# LAUNCHXL-F28377S_3.net
KiCad netlist of a schematic drawn in Altium Designer
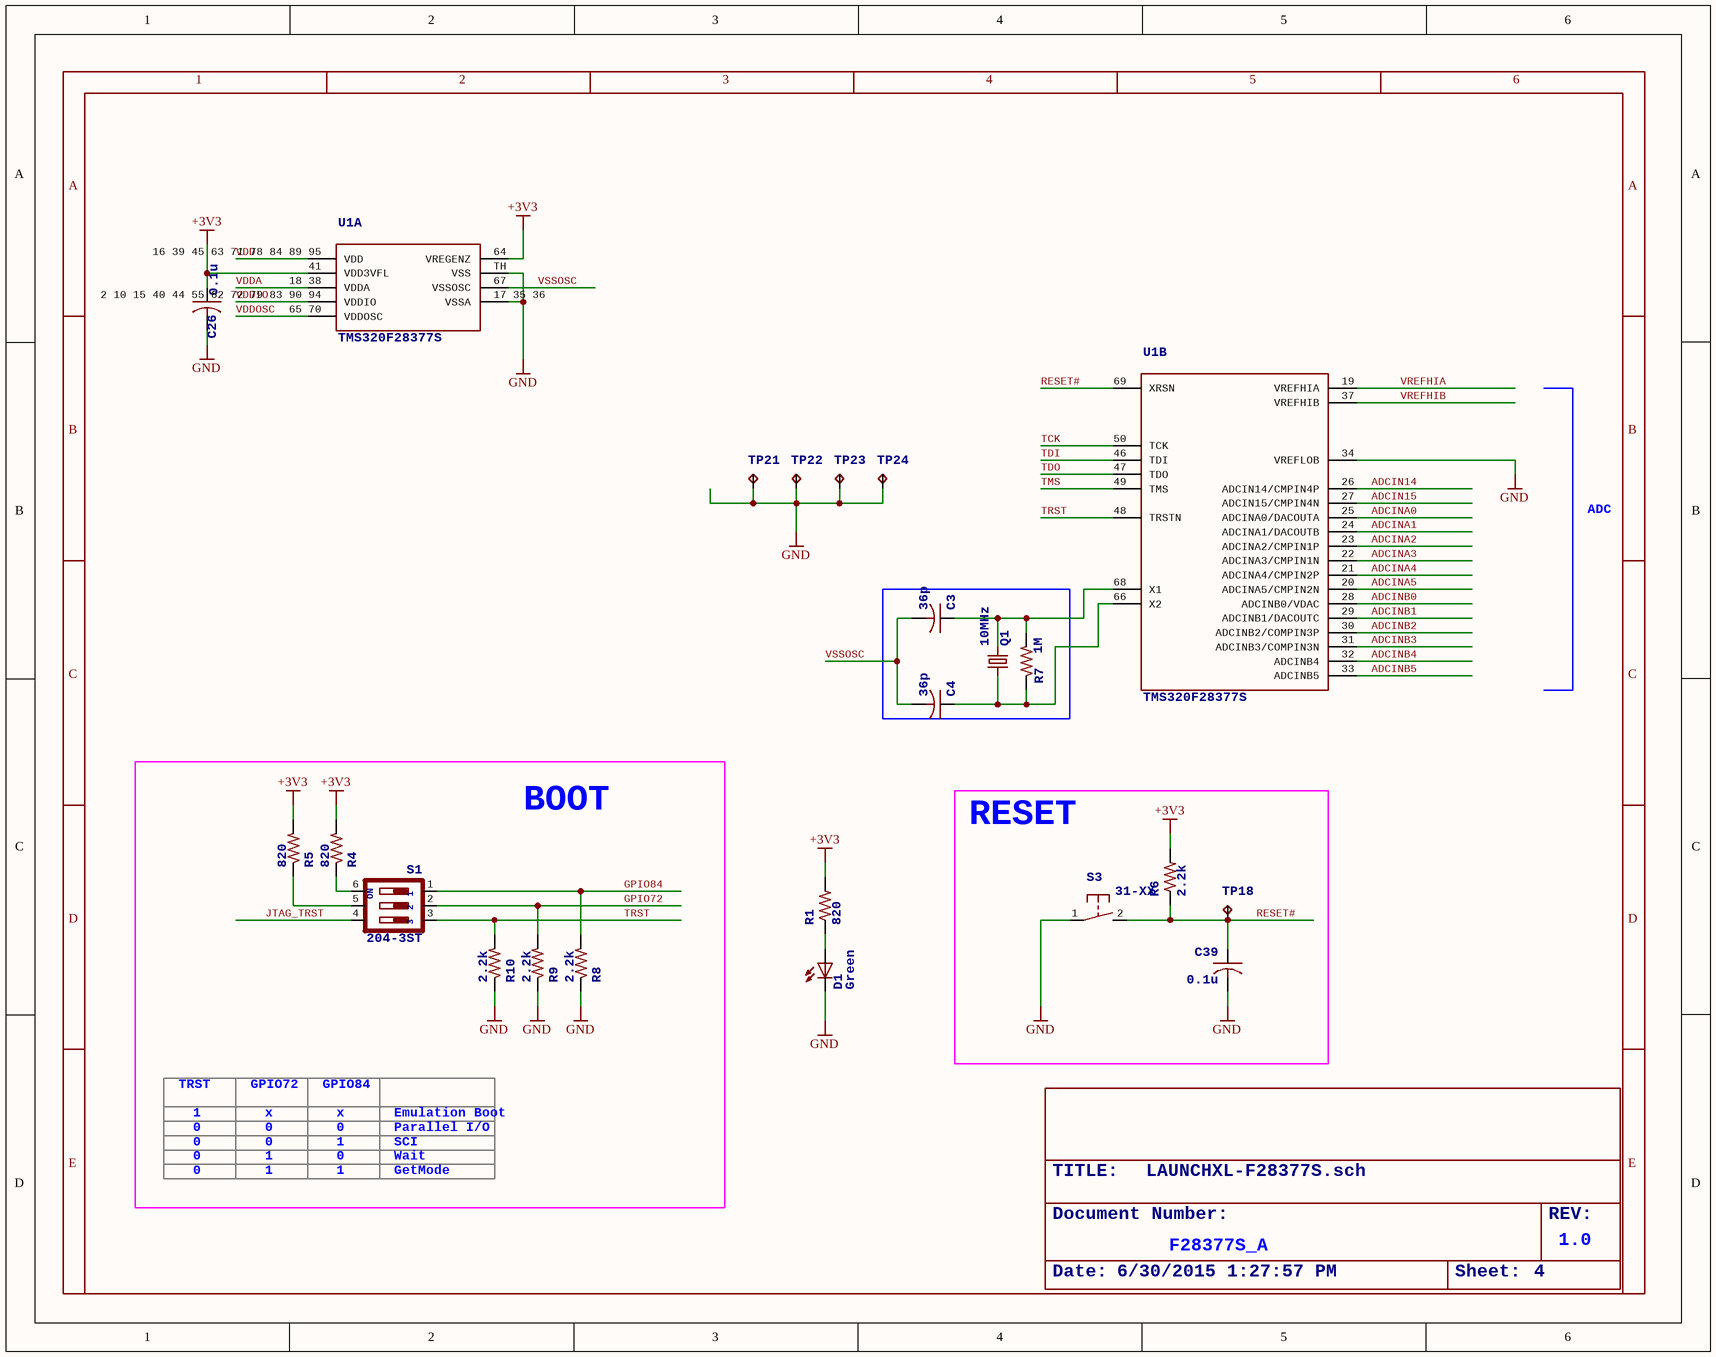
[diagram p0: LAUNCHXL-F28377S_3.SchDoc]

(export (version "E")
  (design (tool "Eeschema 10.0.6"))
  (components
    (comp (ref "C3")
      (value "36p")
      (footprint "C0402")
      (description "<B>CAPACITOR</B>, American symbol")
      (libsource (lib "rcl") (part "C-USC0402"))
    )
    (comp (ref "C4")
      (value "36p")
      (footprint "C0402")
      (description "<B>CAPACITOR</B>, American symbol")
      (libsource (lib "rcl") (part "C-USC0402"))
    )
    (comp (ref "C26")
      (value "0.1u")
      (footprint "C0402")
      (description "<B>CAPACITOR</B>, American symbol")
      (libsource (lib "rcl") (part "C-USC0402"))
    )
    (comp (ref "C39")
      (value "0.1u")
      (footprint "C0402")
      (description "<B>CAPACITOR</B>, American symbol")
      (libsource (lib "rcl") (part "C-USC0402"))
    )
    (comp (ref "D1")
      (value "Green")
      (footprint "CHIP-LED0603")
      (libsource (lib "led") (part "LEDCHIP-LED0603"))
    )
    (comp (ref "Q1")
      (value "10MHz")
      (footprint "HC49/S")
      (description "<b>CRYSTAL</b>")
      (libsource (lib "crystal") (part "CRYSTALHC49S"))
    )
    (comp (ref "R1")
      (value "820")
      (footprint "R0402")
      (description "<B>RESISTOR</B>, American symbol")
      (libsource (lib "rcl") (part "R-US_R0402"))
    )
    (comp (ref "R4")
      (value "820")
      (footprint "R0402")
      (description "<B>RESISTOR</B>, American symbol")
      (libsource (lib "rcl") (part "R-US_R0402"))
    )
    (comp (ref "R5")
      (value "820")
      (footprint "R0402")
      (description "<B>RESISTOR</B>, American symbol")
      (libsource (lib "rcl") (part "R-US_R0402"))
    )
    (comp (ref "R6")
      (value "2.2k")
      (footprint "R0402")
      (description "<B>RESISTOR</B>, American symbol")
      (libsource (lib "rcl") (part "R-US_R0402"))
    )
    (comp (ref "R7")
      (value "1M")
      (footprint "R0402")
      (description "<B>RESISTOR</B>, American symbol")
      (libsource (lib "rcl") (part "R-US_R0402"))
    )
    (comp (ref "R8")
      (value "2.2k")
      (footprint "R0402")
      (description "<B>RESISTOR</B>, American symbol")
      (libsource (lib "rcl") (part "R-US_R0402"))
    )
    (comp (ref "R9")
      (value "2.2k")
      (footprint "R0402")
      (description "<B>RESISTOR</B>, American symbol")
      (libsource (lib "rcl") (part "R-US_R0402"))
    )
    (comp (ref "R10")
      (value "2.2k")
      (footprint "R0402")
      (description "<B>RESISTOR</B>, American symbol")
      (libsource (lib "rcl") (part "R-US_R0402"))
    )
    (comp (ref "S1")
      (value "204-3ST")
      (footprint "CTS-219-03")
      (fields (field (name "1") "1") (field (name "2") "2") (field (name "3") "3") (field (name "ON") "ON"))
      (libsource (lib "switch-dil") (part "219-03*"))
    )
    (comp (ref "S3")
      (value "31-XX")
      (footprint "B3F-31XX")
      (description "<b>OMRON SWITCH</b>")
      (fields (field (name "MPN") "B3F-3100"))
      (libsource (lib "switch-omron") (part "31-XX"))
    )
    (comp (ref "TP18")
      (value "TESTPAD_TPB1,27")
      (footprint "TESTPAD_B1,27")
      (description "<b>Test pad</b>")
      (libsource (lib "RF430FRL152H_EVM_a") (part "TESTPAD_TPB1,27"))
    )
    (comp (ref "TP21")
      (value "TESTPAD_TPB1,27")
      (footprint "TESTPAD_B1,27")
      (description "<b>Test pad</b>")
      (libsource (lib "RF430FRL152H_EVM_a") (part "TESTPAD_TPB1,27"))
    )
    (comp (ref "TP22")
      (value "TESTPAD_TPB1,27")
      (footprint "TESTPAD_B1,27")
      (description "<b>Test pad</b>")
      (libsource (lib "RF430FRL152H_EVM_a") (part "TESTPAD_TPB1,27"))
    )
    (comp (ref "TP23")
      (value "TESTPAD_TPB1,27")
      (footprint "TESTPAD_B1,27")
      (description "<b>Test pad</b>")
      (libsource (lib "RF430FRL152H_EVM_a") (part "TESTPAD_TPB1,27"))
    )
    (comp (ref "TP24")
      (value "TESTPAD_TPB1,27")
      (footprint "TESTPAD_B1,27")
      (description "<b>Test pad</b>")
      (libsource (lib "RF430FRL152H_EVM_a") (part "TESTPAD_TPB1,27"))
    )
    (comp (ref "U1")
      (value "TMS320F28377S")
      (footprint "PQFP100_THERMAL")
      (libsource (lib "LAUNCHXL-F28377S") (part "TMS320F28377S"))
    )
  )
  (nets
    (net (code "1") (name "+3V3") (class "Default")
      (node (ref "C26") (pin "1") (pinfunction "1_1") (pintype "passive"))
      (node (ref "R1") (pin "2") (pinfunction "2_2") (pintype "passive"))
      (node (ref "R4") (pin "2") (pinfunction "2_2") (pintype "passive"))
      (node (ref "R5") (pin "2") (pinfunction "2_2") (pintype "passive"))
      (node (ref "R6") (pin "2") (pinfunction "2_2") (pintype "passive"))
      (node (ref "U1") (pin "41") (pinfunction "VDD3VFL_41") (pintype "passive"))
      (node (ref "U1") (pin "64") (pinfunction "VREGENZ_64") (pintype "passive"))
    )
    (net (code "2") (name "/ADCIN14") (class "Default")
      (node (ref "U1") (pin "26") (pinfunction "ADCIN14/CMPIN4P_26") (pintype "passive"))
    )
    (net (code "3") (name "/ADCIN15") (class "Default")
      (node (ref "U1") (pin "27") (pinfunction "ADCIN15/CMPIN4N_27") (pintype "passive"))
    )
    (net (code "4") (name "/ADCINA0") (class "Default")
      (node (ref "U1") (pin "25") (pinfunction "ADCINA0/DACOUTA_25") (pintype "passive"))
    )
    (net (code "5") (name "/ADCINA1") (class "Default")
      (node (ref "U1") (pin "24") (pinfunction "ADCINA1/DACOUTB_24") (pintype "passive"))
    )
    (net (code "6") (name "/ADCINA2") (class "Default")
      (node (ref "U1") (pin "23") (pinfunction "ADCINA2/CMPIN1P_23") (pintype "passive"))
    )
    (net (code "7") (name "/ADCINA3") (class "Default")
      (node (ref "U1") (pin "22") (pinfunction "ADCINA3/CMPIN1N_22") (pintype "passive"))
    )
    (net (code "8") (name "/ADCINA4") (class "Default")
      (node (ref "U1") (pin "21") (pinfunction "ADCINA4/CMPIN2P_21") (pintype "passive"))
    )
    (net (code "9") (name "/ADCINA5") (class "Default")
      (node (ref "U1") (pin "20") (pinfunction "ADCINA5/CMPIN2N_20") (pintype "passive"))
    )
    (net (code "10") (name "/ADCINB0") (class "Default")
      (node (ref "U1") (pin "28") (pinfunction "ADCINB0/VDAC_28") (pintype "passive"))
    )
    (net (code "11") (name "/ADCINB1") (class "Default")
      (node (ref "U1") (pin "29") (pinfunction "ADCINB1/DACOUTC_29") (pintype "passive"))
    )
    (net (code "12") (name "/ADCINB2") (class "Default")
      (node (ref "U1") (pin "30") (pinfunction "ADCINB2/COMPIN3P_30") (pintype "passive"))
    )
    (net (code "13") (name "/ADCINB3") (class "Default")
      (node (ref "U1") (pin "31") (pinfunction "ADCINB3/COMPIN3N_31") (pintype "passive"))
    )
    (net (code "14") (name "/ADCINB4") (class "Default")
      (node (ref "U1") (pin "32") (pinfunction "ADCINB4_32") (pintype "passive"))
    )
    (net (code "15") (name "/ADCINB5") (class "Default")
      (node (ref "U1") (pin "33") (pinfunction "ADCINB5_33") (pintype "passive"))
    )
    (net (code "16") (name "/GPIO72") (class "Default")
      (node (ref "R9") (pin "2") (pinfunction "2_2") (pintype "passive"))
      (node (ref "S1") (pin "2") (pinfunction "2_2") (pintype "passive"))
    )
    (net (code "17") (name "/GPIO84") (class "Default")
      (node (ref "R8") (pin "2") (pinfunction "2_2") (pintype "passive"))
      (node (ref "S1") (pin "1") (pinfunction "1_1") (pintype "passive"))
    )
    (net (code "18") (name "/JTAG_TRST") (class "Default")
      (node (ref "S1") (pin "4") (pinfunction "4_4") (pintype "passive"))
    )
    (net (code "19") (name "/RESET#") (class "Default")
      (node (ref "C39") (pin "1") (pinfunction "1_1") (pintype "passive"))
      (node (ref "R6") (pin "1") (pinfunction "1_1") (pintype "passive"))
      (node (ref "S3") (pin "2") (pinfunction "S_2") (pintype "passive"))
      (node (ref "TP18") (pin "TP") (pinfunction "TP_TP") (pintype "passive"))
      (node (ref "U1") (pin "69") (pinfunction "XRSN_69") (pintype "passive"))
    )
    (net (code "20") (name "/TCK") (class "Default")
      (node (ref "U1") (pin "50") (pinfunction "TCK_50") (pintype "passive"))
    )
    (net (code "21") (name "/TDI") (class "Default")
      (node (ref "U1") (pin "46") (pinfunction "TDI_46") (pintype "passive"))
    )
    (net (code "22") (name "/TDO") (class "Default")
      (node (ref "U1") (pin "47") (pinfunction "TDO_47") (pintype "passive"))
    )
    (net (code "23") (name "/TMS") (class "Default")
      (node (ref "U1") (pin "49") (pinfunction "TMS_49") (pintype "passive"))
    )
    (net (code "24") (name "/TRST") (class "Default")
      (node (ref "R10") (pin "2") (pinfunction "2_2") (pintype "passive"))
      (node (ref "S1") (pin "3") (pinfunction "3_3") (pintype "passive"))
      (node (ref "U1") (pin "48") (pinfunction "TRSTN_48") (pintype "passive"))
    )
    (net (code "25") (name "/VDD") (class "Default")
      (node (ref "U1") (pin "16_39_45_63_71_78_84_89_95") (pinfunction "VDD_16_39_45_63_71_78_84_89_95") (pintype "passive"))
    )
    (net (code "26") (name "/VDDA") (class "Default")
      (node (ref "U1") (pin "18_38") (pinfunction "VDDA_18_38") (pintype "passive"))
    )
    (net (code "27") (name "/VDDIO") (class "Default")
      (node (ref "U1") (pin "2_10_15_40_44_55_62_72_79_83_90_94") (pinfunction "VDDIO_2_10_15_40_44_55_62_72_79_83_90_94") (pintype "passive"))
    )
    (net (code "28") (name "/VDDOSC") (class "Default")
      (node (ref "U1") (pin "65_70") (pinfunction "VDDOSC_65_70") (pintype "passive"))
    )
    (net (code "29") (name "/VREFHIA") (class "Default")
      (node (ref "U1") (pin "19") (pinfunction "VREFHIA_19") (pintype "passive"))
    )
    (net (code "30") (name "/VREFHIB") (class "Default")
      (node (ref "U1") (pin "37") (pinfunction "VREFHIB_37") (pintype "passive"))
    )
    (net (code "31") (name "/VSSOSC") (class "Default")
      (node (ref "C3") (pin "2") (pinfunction "2_2") (pintype "passive"))
      (node (ref "C4") (pin "2") (pinfunction "2_2") (pintype "passive"))
      (node (ref "U1") (pin "67") (pinfunction "VSSOSC_67") (pintype "passive"))
    )
    (net (code "32") (name "GND") (class "Default")
      (node (ref "C26") (pin "2") (pinfunction "2_2") (pintype "passive"))
      (node (ref "C39") (pin "2") (pinfunction "2_2") (pintype "passive"))
      (node (ref "D1") (pin "C") (pinfunction "C_C") (pintype "passive"))
      (node (ref "R10") (pin "1") (pinfunction "1_1") (pintype "passive"))
      (node (ref "R8") (pin "1") (pinfunction "1_1") (pintype "passive"))
      (node (ref "R9") (pin "1") (pinfunction "1_1") (pintype "passive"))
      (node (ref "S3") (pin "1") (pinfunction "P_1") (pintype "passive"))
      (node (ref "TP21") (pin "TP") (pinfunction "TP_TP") (pintype "passive"))
      (node (ref "TP22") (pin "TP") (pinfunction "TP_TP") (pintype "passive"))
      (node (ref "TP23") (pin "TP") (pinfunction "TP_TP") (pintype "passive"))
      (node (ref "TP24") (pin "TP") (pinfunction "TP_TP") (pintype "passive"))
      (node (ref "U1") (pin "17_35_36") (pinfunction "VSSA_17_35_36") (pintype "passive"))
      (node (ref "U1") (pin "34") (pinfunction "VREFLOB_34") (pintype "passive"))
      (node (ref "U1") (pin "TH") (pinfunction "VSS_TH") (pintype "passive"))
    )
    (net (code "33") (name "Net-(D1-PadA)") (class "Default")
      (node (ref "D1") (pin "A") (pinfunction "A_A") (pintype "passive"))
      (node (ref "R1") (pin "1") (pinfunction "1_1") (pintype "passive"))
    )
    (net (code "34") (name "Net-(R4-Pad1)") (class "Default")
      (node (ref "R4") (pin "1") (pinfunction "1_1") (pintype "passive"))
      (node (ref "S1") (pin "6") (pinfunction "6_6") (pintype "passive"))
    )
    (net (code "35") (name "Net-(R5-Pad1)") (class "Default")
      (node (ref "R5") (pin "1") (pinfunction "1_1") (pintype "passive"))
      (node (ref "S1") (pin "5") (pinfunction "5_5") (pintype "passive"))
    )
    (net (code "36") (name "Net-(U1B-X1)") (class "Default")
      (node (ref "C3") (pin "1") (pinfunction "1_1") (pintype "passive"))
      (node (ref "Q1") (pin "2") (pinfunction "2_2") (pintype "passive"))
      (node (ref "R7") (pin "2") (pinfunction "2_2") (pintype "passive"))
      (node (ref "U1") (pin "68") (pinfunction "X1_68") (pintype "passive"))
    )
    (net (code "37") (name "Net-(U1B-X2)") (class "Default")
      (node (ref "C4") (pin "1") (pinfunction "1_1") (pintype "passive"))
      (node (ref "Q1") (pin "1") (pinfunction "1_1") (pintype "passive"))
      (node (ref "R7") (pin "1") (pinfunction "1_1") (pintype "passive"))
      (node (ref "U1") (pin "66") (pinfunction "X2_66") (pintype "passive"))
    )
  )
)
